# Prototype.net
KiCad netlist of a schematic drawn in EAGLE
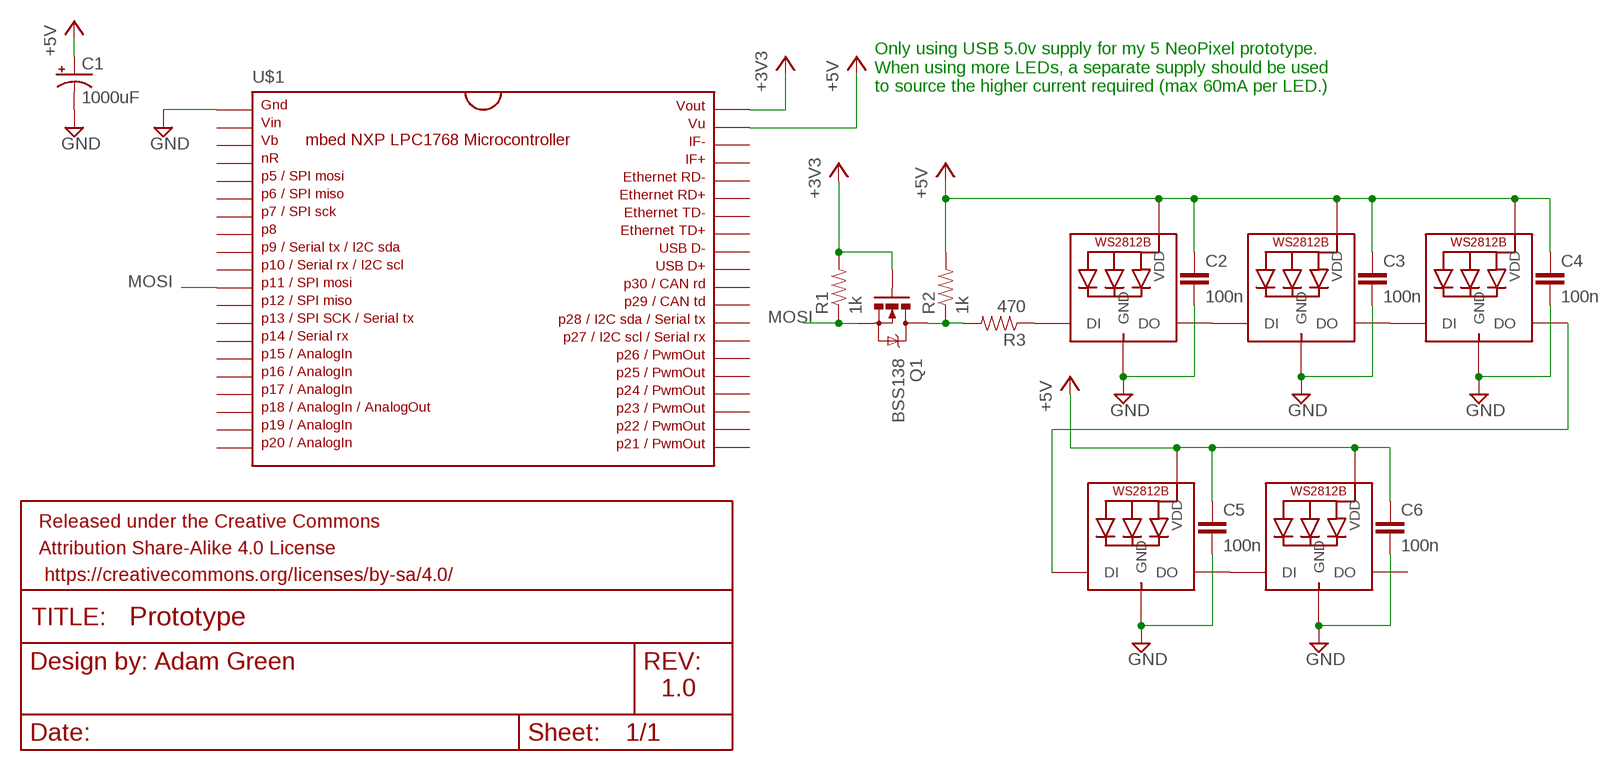
[diagram p0: schematic, sheet 1]

(export (version "E")
  (design (tool "Eeschema 10.0.6"))
  (components
    (comp (ref "C1")
      (value "1000uF")
      (footprint "eagle-import:CPOL-RADIAL-1000UF-25V")
      (libsource (lib "eagle-import") (part "CAP_POLPTH4"))
    )
    (comp (ref "C2")
      (value "100n")
      (footprint "eagle-import:0805")
      (libsource (lib "eagle-import") (part "CAP0805"))
    )
    (comp (ref "C3")
      (value "100n")
      (footprint "eagle-import:0805")
      (libsource (lib "eagle-import") (part "CAP0805"))
    )
    (comp (ref "C4")
      (value "100n")
      (footprint "eagle-import:0805")
      (libsource (lib "eagle-import") (part "CAP0805"))
    )
    (comp (ref "C5")
      (value "100n")
      (footprint "eagle-import:0805")
      (libsource (lib "eagle-import") (part "CAP0805"))
    )
    (comp (ref "C6")
      (value "100n")
      (footprint "eagle-import:0805")
      (libsource (lib "eagle-import") (part "CAP0805"))
    )
    (comp (ref "LED1")
      (value "WS2812B3535")
      (footprint "eagle-import:LED3535")
      (libsource (lib "eagle-import") (part "WS2812B3535"))
    )
    (comp (ref "LED2")
      (value "WS2812B3535")
      (footprint "eagle-import:LED3535")
      (libsource (lib "eagle-import") (part "WS2812B3535"))
    )
    (comp (ref "LED4")
      (value "WS2812B3535")
      (footprint "eagle-import:LED3535")
      (libsource (lib "eagle-import") (part "WS2812B3535"))
    )
    (comp (ref "LED5")
      (value "WS2812B3535")
      (footprint "eagle-import:LED3535")
      (libsource (lib "eagle-import") (part "WS2812B3535"))
    )
    (comp (ref "LED6")
      (value "WS2812B3535")
      (footprint "eagle-import:LED3535")
      (libsource (lib "eagle-import") (part "WS2812B3535"))
    )
    (comp (ref "Q1")
      (value "BSS138")
      (footprint "eagle-import:SOT23-3")
      (libsource (lib "eagle-import") (part "MOSFET-NCHANNELBSS138"))
    )
    (comp (ref "R1")
      (value "1k")
      (footprint "eagle-import:0805")
      (libsource (lib "eagle-import") (part "RESISTOR0805-RES"))
    )
    (comp (ref "R2")
      (value "1k")
      (footprint "eagle-import:0805")
      (libsource (lib "eagle-import") (part "RESISTOR0805-RES"))
    )
    (comp (ref "R3")
      (value "470")
      (footprint "eagle-import:0805")
      (libsource (lib "eagle-import") (part "RESISTOR0805-RES"))
    )
    (comp (ref "U$1")
      (value "MBED_NXP_LPC1768")
      (footprint "eagle-import:DIL40_0.9")
      (libsource (lib "eagle-import") (part "MBED_NXP_LPC1768"))
    )
  )
  (nets
    (net (code "1") (name "+3V3") (class "Default")
      (node (ref "Q1") (pin "1") (pinfunction "G_1") (pintype "passive"))
      (node (ref "R1") (pin "2") (pinfunction "2_2") (pintype "passive"))
      (node (ref "U$1") (pin "40") (pinfunction "P$40_40") (pintype "bidirectional"))
    )
    (net (code "2") (name "+5V") (class "Default")
      (node (ref "C1") (pin "1") (pinfunction "+_1") (pintype "passive"))
      (node (ref "C2") (pin "1") (pinfunction "1_1") (pintype "passive"))
      (node (ref "C3") (pin "1") (pinfunction "1_1") (pintype "passive"))
      (node (ref "C4") (pin "1") (pinfunction "1_1") (pintype "passive"))
      (node (ref "C5") (pin "1") (pinfunction "1_1") (pintype "passive"))
      (node (ref "C6") (pin "1") (pinfunction "1_1") (pintype "passive"))
      (node (ref "LED1") (pin "2") (pinfunction "VDD_2") (pintype "power_in"))
      (node (ref "LED2") (pin "2") (pinfunction "VDD_2") (pintype "power_in"))
      (node (ref "LED4") (pin "2") (pinfunction "VDD_2") (pintype "power_in"))
      (node (ref "LED5") (pin "2") (pinfunction "VDD_2") (pintype "power_in"))
      (node (ref "LED6") (pin "2") (pinfunction "VDD_2") (pintype "power_in"))
      (node (ref "R2") (pin "2") (pinfunction "2_2") (pintype "passive"))
      (node (ref "U$1") (pin "39") (pinfunction "P$39_39") (pintype "bidirectional"))
    )
    (net (code "3") (name "/MOSI") (class "Default")
      (node (ref "Q1") (pin "2") (pinfunction "S_2") (pintype "passive"))
      (node (ref "R1") (pin "1") (pinfunction "1_1") (pintype "passive"))
      (node (ref "U$1") (pin "11") (pinfunction "P$11_11") (pintype "bidirectional"))
    )
    (net (code "4") (name "GND") (class "Default")
      (node (ref "C1") (pin "2") (pinfunction "-_2") (pintype "passive"))
      (node (ref "C2") (pin "2") (pinfunction "2_2") (pintype "passive"))
      (node (ref "C3") (pin "2") (pinfunction "2_2") (pintype "passive"))
      (node (ref "C4") (pin "2") (pinfunction "2_2") (pintype "passive"))
      (node (ref "C5") (pin "2") (pinfunction "2_2") (pintype "passive"))
      (node (ref "C6") (pin "2") (pinfunction "2_2") (pintype "passive"))
      (node (ref "LED1") (pin "4") (pinfunction "GND_4") (pintype "power_in"))
      (node (ref "LED2") (pin "4") (pinfunction "GND_4") (pintype "power_in"))
      (node (ref "LED4") (pin "4") (pinfunction "GND_4") (pintype "power_in"))
      (node (ref "LED5") (pin "4") (pinfunction "GND_4") (pintype "power_in"))
      (node (ref "LED6") (pin "4") (pinfunction "GND_4") (pintype "power_in"))
      (node (ref "U$1") (pin "1") (pinfunction "P$1_1") (pintype "bidirectional"))
    )
    (net (code "5") (name "Net-(LED1-DI)") (class "Default")
      (node (ref "LED1") (pin "1") (pinfunction "DI_1") (pintype "input"))
      (node (ref "R3") (pin "1") (pinfunction "1_1") (pintype "passive"))
    )
    (net (code "6") (name "Net-(LED1-DO)") (class "Default")
      (node (ref "LED1") (pin "3") (pinfunction "DO_3") (pintype "output"))
      (node (ref "LED2") (pin "1") (pinfunction "DI_1") (pintype "input"))
    )
    (net (code "7") (name "Net-(LED2-DO)") (class "Default")
      (node (ref "LED2") (pin "3") (pinfunction "DO_3") (pintype "output"))
      (node (ref "LED4") (pin "1") (pinfunction "DI_1") (pintype "input"))
    )
    (net (code "8") (name "Net-(LED4-DO)") (class "Default")
      (node (ref "LED4") (pin "3") (pinfunction "DO_3") (pintype "output"))
      (node (ref "LED5") (pin "1") (pinfunction "DI_1") (pintype "input"))
    )
    (net (code "9") (name "Net-(LED5-DO)") (class "Default")
      (node (ref "LED5") (pin "3") (pinfunction "DO_3") (pintype "output"))
      (node (ref "LED6") (pin "1") (pinfunction "DI_1") (pintype "input"))
    )
    (net (code "10") (name "Net-(Q1-D)") (class "Default")
      (node (ref "Q1") (pin "3") (pinfunction "D_3") (pintype "passive"))
      (node (ref "R2") (pin "1") (pinfunction "1_1") (pintype "passive"))
      (node (ref "R3") (pin "2") (pinfunction "2_2") (pintype "passive"))
    )
    (net (code "11") (name "unconnected-(LED6-DO-Pad3)") (class "Default")
      (node (ref "LED6") (pin "3") (pinfunction "DO_3") (pintype "output"))
    )
    (net (code "12") (name "unconnected-(U$1-P$2-Pad2)") (class "Default")
      (node (ref "U$1") (pin "2") (pinfunction "P$2_2") (pintype "bidirectional"))
    )
    (net (code "13") (name "unconnected-(U$1-P$3-Pad3)") (class "Default")
      (node (ref "U$1") (pin "3") (pinfunction "P$3_3") (pintype "bidirectional"))
    )
    (net (code "14") (name "unconnected-(U$1-P$4-Pad4)") (class "Default")
      (node (ref "U$1") (pin "4") (pinfunction "P$4_4") (pintype "bidirectional"))
    )
    (net (code "15") (name "unconnected-(U$1-P$5-Pad5)") (class "Default")
      (node (ref "U$1") (pin "5") (pinfunction "P$5_5") (pintype "bidirectional"))
    )
    (net (code "16") (name "unconnected-(U$1-P$6-Pad6)") (class "Default")
      (node (ref "U$1") (pin "6") (pinfunction "P$6_6") (pintype "bidirectional"))
    )
    (net (code "17") (name "unconnected-(U$1-P$7-Pad7)") (class "Default")
      (node (ref "U$1") (pin "7") (pinfunction "P$7_7") (pintype "bidirectional"))
    )
    (net (code "18") (name "unconnected-(U$1-P$8-Pad8)") (class "Default")
      (node (ref "U$1") (pin "8") (pinfunction "P$8_8") (pintype "bidirectional"))
    )
    (net (code "19") (name "unconnected-(U$1-P$9-Pad9)") (class "Default")
      (node (ref "U$1") (pin "9") (pinfunction "P$9_9") (pintype "bidirectional"))
    )
    (net (code "20") (name "unconnected-(U$1-P$10-Pad10)") (class "Default")
      (node (ref "U$1") (pin "10") (pinfunction "P$10_10") (pintype "bidirectional"))
    )
    (net (code "21") (name "unconnected-(U$1-P$12-Pad12)") (class "Default")
      (node (ref "U$1") (pin "12") (pinfunction "P$12_12") (pintype "bidirectional"))
    )
    (net (code "22") (name "unconnected-(U$1-P$13-Pad13)") (class "Default")
      (node (ref "U$1") (pin "13") (pinfunction "P$13_13") (pintype "bidirectional"))
    )
    (net (code "23") (name "unconnected-(U$1-P$14-Pad14)") (class "Default")
      (node (ref "U$1") (pin "14") (pinfunction "P$14_14") (pintype "bidirectional"))
    )
    (net (code "24") (name "unconnected-(U$1-P$15-Pad15)") (class "Default")
      (node (ref "U$1") (pin "15") (pinfunction "P$15_15") (pintype "bidirectional"))
    )
    (net (code "25") (name "unconnected-(U$1-P$16-Pad16)") (class "Default")
      (node (ref "U$1") (pin "16") (pinfunction "P$16_16") (pintype "bidirectional"))
    )
    (net (code "26") (name "unconnected-(U$1-P$17-Pad17)") (class "Default")
      (node (ref "U$1") (pin "17") (pinfunction "P$17_17") (pintype "bidirectional"))
    )
    (net (code "27") (name "unconnected-(U$1-P$18-Pad18)") (class "Default")
      (node (ref "U$1") (pin "18") (pinfunction "P$18_18") (pintype "bidirectional"))
    )
    (net (code "28") (name "unconnected-(U$1-P$19-Pad19)") (class "Default")
      (node (ref "U$1") (pin "19") (pinfunction "P$19_19") (pintype "bidirectional"))
    )
    (net (code "29") (name "unconnected-(U$1-P$20-Pad20)") (class "Default")
      (node (ref "U$1") (pin "20") (pinfunction "P$20_20") (pintype "bidirectional"))
    )
    (net (code "30") (name "unconnected-(U$1-P$21-Pad21)") (class "Default")
      (node (ref "U$1") (pin "21") (pinfunction "P$21_21") (pintype "bidirectional"))
    )
    (net (code "31") (name "unconnected-(U$1-P$22-Pad22)") (class "Default")
      (node (ref "U$1") (pin "22") (pinfunction "P$22_22") (pintype "bidirectional"))
    )
    (net (code "32") (name "unconnected-(U$1-P$23-Pad23)") (class "Default")
      (node (ref "U$1") (pin "23") (pinfunction "P$23_23") (pintype "bidirectional"))
    )
    (net (code "33") (name "unconnected-(U$1-P$24-Pad24)") (class "Default")
      (node (ref "U$1") (pin "24") (pinfunction "P$24_24") (pintype "bidirectional"))
    )
    (net (code "34") (name "unconnected-(U$1-P$25-Pad25)") (class "Default")
      (node (ref "U$1") (pin "25") (pinfunction "P$25_25") (pintype "bidirectional"))
    )
    (net (code "35") (name "unconnected-(U$1-P$26-Pad26)") (class "Default")
      (node (ref "U$1") (pin "26") (pinfunction "P$26_26") (pintype "bidirectional"))
    )
    (net (code "36") (name "unconnected-(U$1-P$27-Pad27)") (class "Default")
      (node (ref "U$1") (pin "27") (pinfunction "P$27_27") (pintype "bidirectional"))
    )
    (net (code "37") (name "unconnected-(U$1-P$28-Pad28)") (class "Default")
      (node (ref "U$1") (pin "28") (pinfunction "P$28_28") (pintype "bidirectional"))
    )
    (net (code "38") (name "unconnected-(U$1-P$29-Pad29)") (class "Default")
      (node (ref "U$1") (pin "29") (pinfunction "P$29_29") (pintype "bidirectional"))
    )
    (net (code "39") (name "unconnected-(U$1-P$30-Pad30)") (class "Default")
      (node (ref "U$1") (pin "30") (pinfunction "P$30_30") (pintype "bidirectional"))
    )
    (net (code "40") (name "unconnected-(U$1-P$31-Pad31)") (class "Default")
      (node (ref "U$1") (pin "31") (pinfunction "P$31_31") (pintype "bidirectional"))
    )
    (net (code "41") (name "unconnected-(U$1-P$32-Pad32)") (class "Default")
      (node (ref "U$1") (pin "32") (pinfunction "P$32_32") (pintype "bidirectional"))
    )
    (net (code "42") (name "unconnected-(U$1-P$33-Pad33)") (class "Default")
      (node (ref "U$1") (pin "33") (pinfunction "P$33_33") (pintype "bidirectional"))
    )
    (net (code "43") (name "unconnected-(U$1-P$34-Pad34)") (class "Default")
      (node (ref "U$1") (pin "34") (pinfunction "P$34_34") (pintype "bidirectional"))
    )
    (net (code "44") (name "unconnected-(U$1-P$35-Pad35)") (class "Default")
      (node (ref "U$1") (pin "35") (pinfunction "P$35_35") (pintype "bidirectional"))
    )
    (net (code "45") (name "unconnected-(U$1-P$36-Pad36)") (class "Default")
      (node (ref "U$1") (pin "36") (pinfunction "P$36_36") (pintype "bidirectional"))
    )
    (net (code "46") (name "unconnected-(U$1-P$37-Pad37)") (class "Default")
      (node (ref "U$1") (pin "37") (pinfunction "P$37_37") (pintype "bidirectional"))
    )
    (net (code "47") (name "unconnected-(U$1-P$38-Pad38)") (class "Default")
      (node (ref "U$1") (pin "38") (pinfunction "P$38_38") (pintype "bidirectional"))
    )
  )
)
